# SSB_Transceiver_LC_Double_Tuned_Bandpass.net
KiCad netlist of a schematic drawn in EAGLE
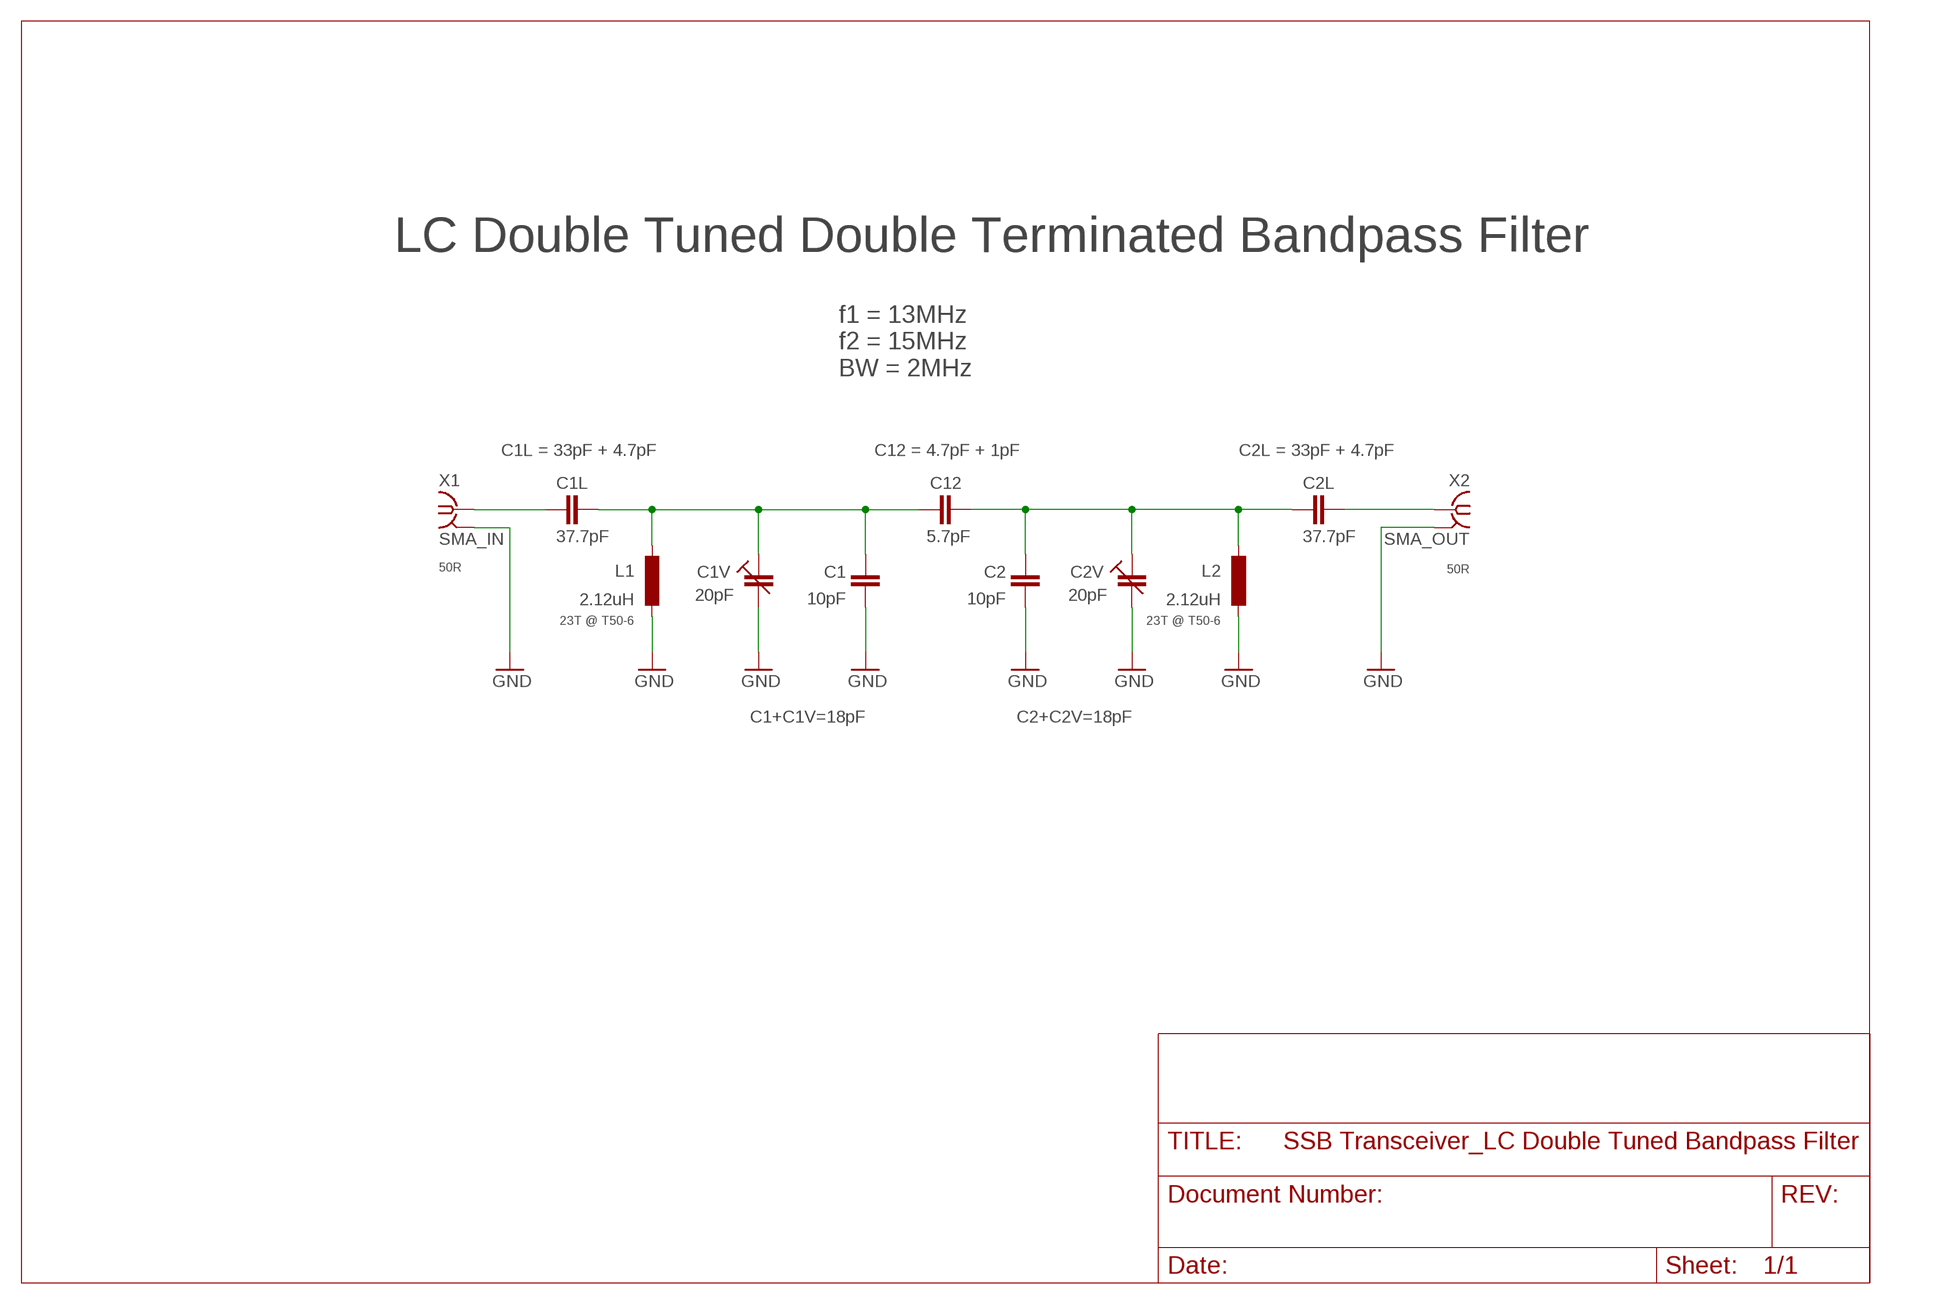
[diagram p0: schematic, sheet 1]

(export (version "E")
  (design (tool "Eeschema 10.0.6"))
  (components
    (comp (ref "C1")
      (value "10pF")
      (footprint "eagle-import:C0805")
      (libsource (lib "eagle-import") (part "C-EUC0805"))
    )
    (comp (ref "C1L")
      (value "37.7pF")
      (footprint "eagle-import:C0805")
      (libsource (lib "eagle-import") (part "C-EUC0805"))
    )
    (comp (ref "C1V")
      (value "20pF")
      (footprint "eagle-import:VARIABLECAP-SMD")
      (libsource (lib "eagle-import") (part "VARIABLECAP"))
    )
    (comp (ref "C2")
      (value "10pF")
      (footprint "eagle-import:C0805")
      (libsource (lib "eagle-import") (part "C-EUC0805"))
    )
    (comp (ref "C2L")
      (value "37.7pF")
      (footprint "eagle-import:C0805")
      (libsource (lib "eagle-import") (part "C-EUC0805"))
    )
    (comp (ref "C2V")
      (value "20pF")
      (footprint "eagle-import:VARIABLECAP-SMD")
      (libsource (lib "eagle-import") (part "VARIABLECAP"))
    )
    (comp (ref "C12")
      (value "5.7pF")
      (footprint "eagle-import:C0805")
      (libsource (lib "eagle-import") (part "C-EUC0805"))
    )
    (comp (ref "L1")
      (value "2.12uH")
      (footprint "eagle-import:T50-6SMD")
      (libsource (lib "eagle-import") (part "T50-6"))
    )
    (comp (ref "L2")
      (value "2.12uH")
      (footprint "eagle-import:T50-6SMD")
      (libsource (lib "eagle-import") (part "T50-6"))
    )
    (comp (ref "X1")
      (value "SMA_IN")
      (footprint "eagle-import:J502-ND-142-0711-821_826")
      (fields (field (name "MF") "JOHNSON COMPONENTS") (field (name "MPN") "142-0711-821"))
      (libsource (lib "eagle-import") (part "SMA-142-0711-821/826"))
    )
    (comp (ref "X2")
      (value "SMA_OUT")
      (footprint "eagle-import:J502-ND-142-0711-821_826")
      (fields (field (name "MF") "JOHNSON COMPONENTS") (field (name "MPN") "142-0711-821"))
      (libsource (lib "eagle-import") (part "SMA-142-0711-821/826"))
    )
  )
  (nets
    (net (code "1") (name "GND") (class "Default")
      (node (ref "C1") (pin "1") (pinfunction "1_1") (pintype "passive"))
      (node (ref "C1V") (pin "P$2") (pinfunction "A_P$2") (pintype "passive"))
      (node (ref "C2") (pin "1") (pinfunction "1_1") (pintype "passive"))
      (node (ref "C2V") (pin "P$2") (pinfunction "A_P$2") (pintype "passive"))
      (node (ref "L1") (pin "P$2") (pinfunction "2_P$2") (pintype "passive"))
      (node (ref "L2") (pin "P$2") (pinfunction "2_P$2") (pintype "passive"))
      (node (ref "X1") (pin "G@1") (pinfunction "2_G@1") (pintype "passive"))
      (node (ref "X1") (pin "G@2") (pinfunction "2_G@2") (pintype "passive"))
      (node (ref "X1") (pin "G@3") (pinfunction "2_G@3") (pintype "passive"))
      (node (ref "X1") (pin "G@4") (pinfunction "2_G@4") (pintype "passive"))
      (node (ref "X2") (pin "G@1") (pinfunction "2_G@1") (pintype "passive"))
      (node (ref "X2") (pin "G@2") (pinfunction "2_G@2") (pintype "passive"))
      (node (ref "X2") (pin "G@3") (pinfunction "2_G@3") (pintype "passive"))
      (node (ref "X2") (pin "G@4") (pinfunction "2_G@4") (pintype "passive"))
    )
    (net (code "2") (name "Net-(C1L-Pad1)") (class "Default")
      (node (ref "C1L") (pin "1") (pinfunction "1_1") (pintype "passive"))
      (node (ref "X1") (pin "1") (pinfunction "1_1") (pintype "passive"))
    )
    (net (code "3") (name "Net-(C1V-E)") (class "Default")
      (node (ref "C1") (pin "2") (pinfunction "2_2") (pintype "passive"))
      (node (ref "C12") (pin "1") (pinfunction "1_1") (pintype "passive"))
      (node (ref "C1L") (pin "2") (pinfunction "2_2") (pintype "passive"))
      (node (ref "C1V") (pin "P$1") (pinfunction "E_P$1") (pintype "passive"))
      (node (ref "L1") (pin "P$1") (pinfunction "1_P$1") (pintype "passive"))
    )
    (net (code "4") (name "Net-(C2L-Pad1)") (class "Default")
      (node (ref "C2L") (pin "1") (pinfunction "1_1") (pintype "passive"))
      (node (ref "X2") (pin "1") (pinfunction "1_1") (pintype "passive"))
    )
    (net (code "5") (name "Net-(C2V-E)") (class "Default")
      (node (ref "C12") (pin "2") (pinfunction "2_2") (pintype "passive"))
      (node (ref "C2") (pin "2") (pinfunction "2_2") (pintype "passive"))
      (node (ref "C2L") (pin "2") (pinfunction "2_2") (pintype "passive"))
      (node (ref "C2V") (pin "P$1") (pinfunction "E_P$1") (pintype "passive"))
      (node (ref "L2") (pin "P$1") (pinfunction "1_P$1") (pintype "passive"))
    )
  )
)
